# MCU_Block.net
KiCad netlist of a schematic drawn in Altium Designer
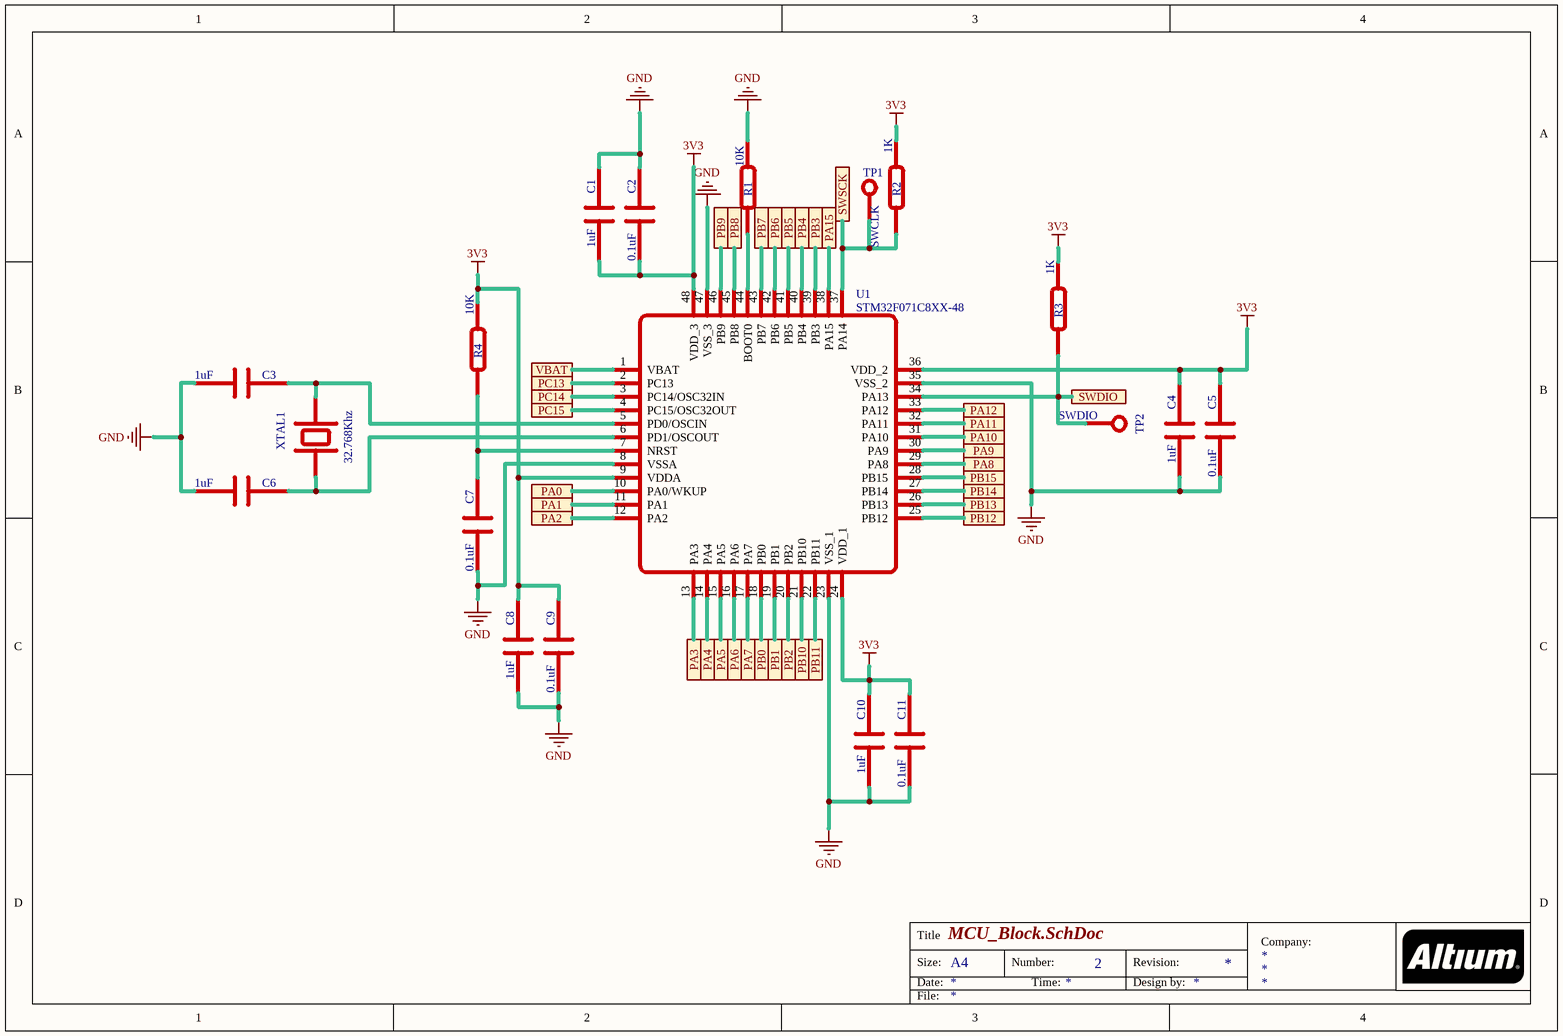
[diagram p0: MCU_Block.SchDoc]

(export (version "E")
  (design (tool "Eeschema 10.0.6"))
  (components
    (comp (ref "C1")
      (value "1uF")
      (footprint "C0603")
      (description "Ceramic Capacitor")
      (libsource (lib "CTAI-Library") (part "CAP-CER"))
    )
    (comp (ref "C2")
      (value "0.1uF")
      (footprint "C0603")
      (description "Ceramic Capacitor")
      (libsource (lib "CTAI-Library") (part "CAP-CER"))
    )
    (comp (ref "C3")
      (value "1uF")
      (footprint "C0603")
      (description "Ceramic Capacitor")
      (libsource (lib "CTAI-Library") (part "CAP-CER"))
    )
    (comp (ref "C4")
      (value "1uF")
      (footprint "C0603")
      (description "Ceramic Capacitor")
      (libsource (lib "CTAI-Library") (part "CAP-CER"))
    )
    (comp (ref "C5")
      (value "0.1uF")
      (footprint "C0603")
      (description "Ceramic Capacitor")
      (libsource (lib "CTAI-Library") (part "CAP-CER"))
    )
    (comp (ref "C6")
      (value "1uF")
      (footprint "C0603")
      (description "Ceramic Capacitor")
      (libsource (lib "CTAI-Library") (part "CAP-CER"))
    )
    (comp (ref "C7")
      (value "0.1uF")
      (footprint "C0603")
      (description "Ceramic Capacitor")
      (libsource (lib "CTAI-Library") (part "CAP-CER"))
    )
    (comp (ref "C8")
      (value "1uF")
      (footprint "C0603")
      (description "Ceramic Capacitor")
      (libsource (lib "CTAI-Library") (part "CAP-CER"))
    )
    (comp (ref "C9")
      (value "0.1uF")
      (footprint "C0603")
      (description "Ceramic Capacitor")
      (libsource (lib "CTAI-Library") (part "CAP-CER"))
    )
    (comp (ref "C10")
      (value "1uF")
      (footprint "C0603")
      (description "Ceramic Capacitor")
      (libsource (lib "CTAI-Library") (part "CAP-CER"))
    )
    (comp (ref "C11")
      (value "0.1uF")
      (footprint "C0603")
      (description "Ceramic Capacitor")
      (libsource (lib "CTAI-Library") (part "CAP-CER"))
    )
    (comp (ref "R1")
      (value "10K")
      (footprint "R0603")
      (description "Resistor")
      (libsource (lib "CTAI-Library") (part "Resistor"))
    )
    (comp (ref "R2")
      (value "1K")
      (footprint "R0603")
      (description "Resistor")
      (libsource (lib "CTAI-Library") (part "Resistor"))
    )
    (comp (ref "R3")
      (value "1K")
      (footprint "R0603")
      (description "Resistor")
      (libsource (lib "CTAI-Library") (part "Resistor"))
    )
    (comp (ref "R4")
      (value "10K")
      (footprint "R0603")
      (description "Resistor")
      (libsource (lib "CTAI-Library") (part "Resistor"))
    )
    (comp (ref "TP1")
      (value "SWCLK")
      (footprint "Test Point")
      (description "Test Point")
      (libsource (lib "CTAI-Library") (part "TestPoint"))
    )
    (comp (ref "TP2")
      (value "SWDIO")
      (footprint "Test Point")
      (description "Test Point")
      (libsource (lib "CTAI-Library") (part "TestPoint"))
    )
    (comp (ref "U1")
      (value "STM32F071C8XX-48")
      (footprint "LQFP48")
      (description "STM32F071C8T6-48Pin")
      (libsource (lib "CTAI-Library") (part "STM32F071C8XX-48"))
    )
    (comp (ref "XTAL1")
      (value "32.768Khz")
      (footprint "Crystal TH HC49")
      (description "Crystall 2Pin Capacitor Intergrated")
      (libsource (lib "CTAI-Library") (part "CRYSTAL-2P"))
    )
  )
  (nets
    (net (code "1") (name "/PA0") (class "Default")
      (node (ref "U1") (pin "10") (pinfunction "PA0/WKUP_10") (pintype "passive"))
    )
    (net (code "2") (name "/PA1") (class "Default")
      (node (ref "U1") (pin "11") (pinfunction "PA1_11") (pintype "passive"))
    )
    (net (code "3") (name "/PA2") (class "Default")
      (node (ref "U1") (pin "12") (pinfunction "PA2_12") (pintype "passive"))
    )
    (net (code "4") (name "/PA3") (class "Default")
      (node (ref "U1") (pin "13") (pinfunction "PA3_13") (pintype "passive"))
    )
    (net (code "5") (name "/PA4") (class "Default")
      (node (ref "U1") (pin "14") (pinfunction "PA4_14") (pintype "passive"))
    )
    (net (code "6") (name "/PA5") (class "Default")
      (node (ref "U1") (pin "15") (pinfunction "PA5_15") (pintype "passive"))
    )
    (net (code "7") (name "/PA6") (class "Default")
      (node (ref "U1") (pin "16") (pinfunction "PA6_16") (pintype "passive"))
    )
    (net (code "8") (name "/PA7") (class "Default")
      (node (ref "U1") (pin "17") (pinfunction "PA7_17") (pintype "passive"))
    )
    (net (code "9") (name "/PA8") (class "Default")
      (node (ref "U1") (pin "29") (pinfunction "PA8_29") (pintype "passive"))
    )
    (net (code "10") (name "/PA9") (class "Default")
      (node (ref "U1") (pin "30") (pinfunction "PA9_30") (pintype "passive"))
    )
    (net (code "11") (name "/PA10") (class "Default")
      (node (ref "U1") (pin "31") (pinfunction "PA10_31") (pintype "passive"))
    )
    (net (code "12") (name "/PA11") (class "Default")
      (node (ref "U1") (pin "32") (pinfunction "PA11_32") (pintype "passive"))
    )
    (net (code "13") (name "/PA12") (class "Default")
      (node (ref "U1") (pin "33") (pinfunction "PA12_33") (pintype "passive"))
    )
    (net (code "14") (name "/PA15") (class "Default")
      (node (ref "U1") (pin "38") (pinfunction "PA15_38") (pintype "passive"))
    )
    (net (code "15") (name "/PB0") (class "Default")
      (node (ref "U1") (pin "18") (pinfunction "PB0_18") (pintype "passive"))
    )
    (net (code "16") (name "/PB1") (class "Default")
      (node (ref "U1") (pin "19") (pinfunction "PB1_19") (pintype "passive"))
    )
    (net (code "17") (name "/PB2") (class "Default")
      (node (ref "U1") (pin "20") (pinfunction "PB2_20") (pintype "passive"))
    )
    (net (code "18") (name "/PB3") (class "Default")
      (node (ref "U1") (pin "39") (pinfunction "PB3_39") (pintype "passive"))
    )
    (net (code "19") (name "/PB4") (class "Default")
      (node (ref "U1") (pin "40") (pinfunction "PB4_40") (pintype "passive"))
    )
    (net (code "20") (name "/PB5") (class "Default")
      (node (ref "U1") (pin "41") (pinfunction "PB5_41") (pintype "passive"))
    )
    (net (code "21") (name "/PB6") (class "Default")
      (node (ref "U1") (pin "42") (pinfunction "PB6_42") (pintype "passive"))
    )
    (net (code "22") (name "/PB7") (class "Default")
      (node (ref "U1") (pin "43") (pinfunction "PB7_43") (pintype "passive"))
    )
    (net (code "23") (name "/PB8") (class "Default")
      (node (ref "U1") (pin "45") (pinfunction "PB8_45") (pintype "passive"))
    )
    (net (code "24") (name "/PB9") (class "Default")
      (node (ref "U1") (pin "46") (pinfunction "PB9_46") (pintype "passive"))
    )
    (net (code "25") (name "/PB10") (class "Default")
      (node (ref "U1") (pin "21") (pinfunction "PB10_21") (pintype "passive"))
    )
    (net (code "26") (name "/PB11") (class "Default")
      (node (ref "U1") (pin "22") (pinfunction "PB11_22") (pintype "passive"))
    )
    (net (code "27") (name "/PB12") (class "Default")
      (node (ref "U1") (pin "25") (pinfunction "PB12_25") (pintype "passive"))
    )
    (net (code "28") (name "/PB13") (class "Default")
      (node (ref "U1") (pin "26") (pinfunction "PB13_26") (pintype "passive"))
    )
    (net (code "29") (name "/PB14") (class "Default")
      (node (ref "U1") (pin "27") (pinfunction "PB14_27") (pintype "passive"))
    )
    (net (code "30") (name "/PB15") (class "Default")
      (node (ref "U1") (pin "28") (pinfunction "PB15_28") (pintype "passive"))
    )
    (net (code "31") (name "/PC13") (class "Default")
      (node (ref "U1") (pin "2") (pinfunction "PC13_2") (pintype "passive"))
    )
    (net (code "32") (name "/PC14") (class "Default")
      (node (ref "U1") (pin "3") (pinfunction "PC14/OSC32IN_3") (pintype "passive"))
    )
    (net (code "33") (name "/PC15") (class "Default")
      (node (ref "U1") (pin "4") (pinfunction "PC15/OSC32OUT_4") (pintype "passive"))
    )
    (net (code "34") (name "/SWDIO") (class "Default")
      (node (ref "R3") (pin "1") (pinfunction "1_1") (pintype "passive"))
      (node (ref "TP2") (pin "1") (pinfunction "1_1") (pintype "passive"))
      (node (ref "U1") (pin "34") (pinfunction "PA13_34") (pintype "passive"))
    )
    (net (code "35") (name "/SWSCK") (class "Default")
      (node (ref "R2") (pin "1") (pinfunction "1_1") (pintype "passive"))
      (node (ref "TP1") (pin "1") (pinfunction "1_1") (pintype "passive"))
      (node (ref "U1") (pin "37") (pinfunction "PA14_37") (pintype "passive"))
    )
    (net (code "36") (name "/VBAT") (class "Default")
      (node (ref "U1") (pin "1") (pinfunction "VBAT_1") (pintype "passive"))
    )
    (net (code "37") (name "3V3") (class "Default")
      (node (ref "C1") (pin "1") (pintype "passive"))
      (node (ref "C10") (pin "2") (pintype "passive"))
      (node (ref "C11") (pin "2") (pintype "passive"))
      (node (ref "C2") (pin "1") (pintype "passive"))
      (node (ref "C4") (pin "2") (pintype "passive"))
      (node (ref "C5") (pin "2") (pintype "passive"))
      (node (ref "C8") (pin "2") (pintype "passive"))
      (node (ref "C9") (pin "2") (pintype "passive"))
      (node (ref "R2") (pin "2") (pinfunction "2_2") (pintype "passive"))
      (node (ref "R3") (pin "2") (pinfunction "2_2") (pintype "passive"))
      (node (ref "R4") (pin "2") (pinfunction "2_2") (pintype "passive"))
      (node (ref "U1") (pin "24") (pinfunction "VDD_1_24") (pintype "passive"))
      (node (ref "U1") (pin "36") (pinfunction "VDD_2_36") (pintype "passive"))
      (node (ref "U1") (pin "48") (pinfunction "VDD_3_48") (pintype "passive"))
      (node (ref "U1") (pin "9") (pinfunction "VDDA_9") (pintype "passive"))
    )
    (net (code "38") (name "GND") (class "Default")
      (node (ref "C1") (pin "2") (pintype "passive"))
      (node (ref "C10") (pin "1") (pintype "passive"))
      (node (ref "C11") (pin "1") (pintype "passive"))
      (node (ref "C2") (pin "2") (pintype "passive"))
      (node (ref "C3") (pin "1") (pintype "passive"))
      (node (ref "C4") (pin "1") (pintype "passive"))
      (node (ref "C5") (pin "1") (pintype "passive"))
      (node (ref "C6") (pin "1") (pintype "passive"))
      (node (ref "C7") (pin "1") (pintype "passive"))
      (node (ref "C8") (pin "1") (pintype "passive"))
      (node (ref "C9") (pin "1") (pintype "passive"))
      (node (ref "R1") (pin "2") (pinfunction "2_2") (pintype "passive"))
      (node (ref "U1") (pin "23") (pinfunction "VSS_1_23") (pintype "passive"))
      (node (ref "U1") (pin "35") (pinfunction "VSS_2_35") (pintype "passive"))
      (node (ref "U1") (pin "47") (pinfunction "VSS_3_47") (pintype "passive"))
      (node (ref "U1") (pin "8") (pinfunction "VSSA_8") (pintype "passive"))
    )
    (net (code "39") (name "Net-(U1-BOOT0)") (class "Default")
      (node (ref "R1") (pin "1") (pinfunction "1_1") (pintype "passive"))
      (node (ref "U1") (pin "44") (pinfunction "BOOT0_44") (pintype "passive"))
    )
    (net (code "40") (name "Net-(U1-NRST)") (class "Default")
      (node (ref "C7") (pin "2") (pintype "passive"))
      (node (ref "R4") (pin "1") (pinfunction "1_1") (pintype "passive"))
      (node (ref "U1") (pin "7") (pinfunction "NRST_7") (pintype "passive"))
    )
    (net (code "41") (name "Net-(U1-PD0{slash}OSCIN)") (class "Default")
      (node (ref "C3") (pin "2") (pintype "passive"))
      (node (ref "U1") (pin "5") (pinfunction "PD0/OSCIN_5") (pintype "passive"))
      (node (ref "XTAL1") (pin "2") (pinfunction "2_2") (pintype "passive"))
    )
    (net (code "42") (name "Net-(U1-PD1{slash}OSCOUT)") (class "Default")
      (node (ref "C6") (pin "2") (pintype "passive"))
      (node (ref "U1") (pin "6") (pinfunction "PD1/OSCOUT_6") (pintype "passive"))
      (node (ref "XTAL1") (pin "1") (pinfunction "1_1") (pintype "passive"))
    )
  )
)
